# rc.net
KiCad netlist of a schematic drawn in EAGLE
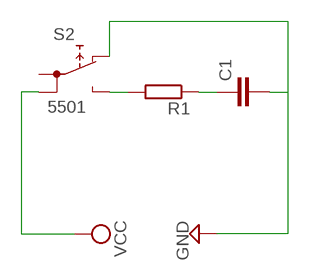
[diagram p0: schematic, sheet 1]

(export (version "E")
  (design (tool "Eeschema 10.0.6"))
  (components
    (comp (ref "C1")
      (value "C5/2.5")
      (footprint "eagle-import:C5B2.5")
      (libsource (lib "eagle-import") (part "C5/2.5"))
    )
    (comp (ref "R1")
      (value "R-EU_0204/5")
      (footprint "eagle-import:0204_5")
      (libsource (lib "eagle-import") (part "R-EU_0204/5"))
    )
    (comp (ref "S2")
      (value "5501")
      (footprint "eagle-import:5501")
      (libsource (lib "eagle-import") (part "55?01"))
    )
  )
  (nets
    (net (code "1") (name "GND") (class "Default")
      (node (ref "C1") (pin "2") (pinfunction "2_2") (pintype "passive"))
      (node (ref "S2") (pin "NC") (pinfunction "NC_NC") (pintype "passive"))
    )
    (net (code "2") (name "Net-(C1-Pad1)") (class "Default")
      (node (ref "C1") (pin "1") (pinfunction "1_1") (pintype "passive"))
      (node (ref "R1") (pin "1") (pinfunction "1_1") (pintype "passive"))
    )
    (net (code "3") (name "Net-(R1-Pad2)") (class "Default")
      (node (ref "R1") (pin "2") (pinfunction "2_2") (pintype "passive"))
      (node (ref "S2") (pin "NO") (pinfunction "NO_NO") (pintype "passive"))
    )
    (net (code "4") (name "VCC") (class "Default")
      (node (ref "S2") (pin "1B") (pinfunction "1B_1B") (pintype "passive"))
    )
    (net (code "5") (name "unconnected-(S2-Pad1A)") (class "Default")
      (node (ref "S2") (pin "1A") (pinfunction "1A_1A") (pintype "passive"))
    )
  )
)
